# PLD_RadFET_Watchdog.net
KiCad netlist of a schematic drawn in Altium Designer
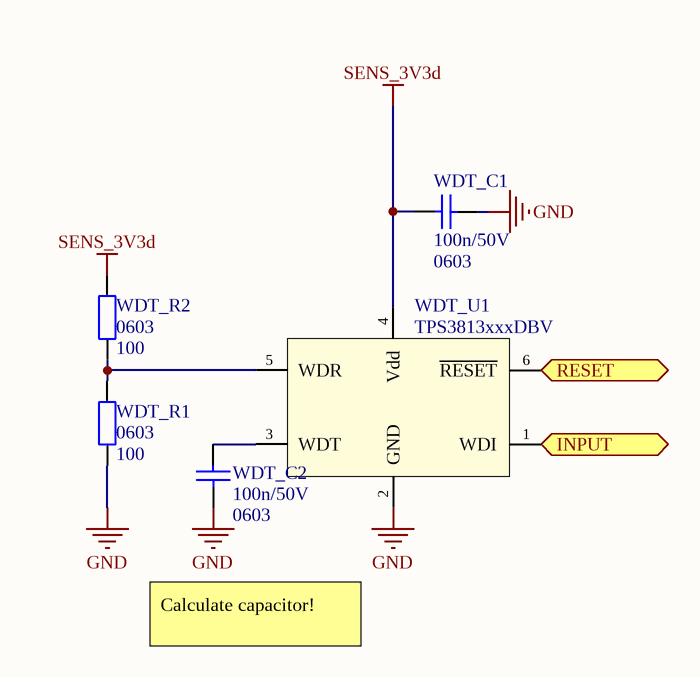
[diagram p0: PLD_RadFET_Watchdog.SchDoc]

(export (version "E")
  (design (tool "Eeschema 10.0.6"))
  (components
    (comp (ref "WDT_C1")
      (value "100n/50V")
      (footprint "SMD_Capacitor_0603")
      (description "Ceramic Cap Kemet COTS 100n/50V X7R 0603")
      (fields
        (field (name "MANUFACTURER") "Kemet")
        (field (name "MANUFACTURERPARTNUMBER") "C0603T104K5RALTU")
        (field (name "PACKAGE") "0603")
      )
      (libsource (lib "capacitors") (part "Cer_C0603T104K5RALTU"))
    )
    (comp (ref "WDT_C2")
      (value "100n/50V")
      (footprint "SMD_Capacitor_0603")
      (description "Ceramic Cap Kemet COTS 100n/50V X7R 0603")
      (fields
        (field (name "MANUFACTURER") "Kemet")
        (field (name "MANUFACTURERPARTNUMBER") "C0603T104K5RALTU")
        (field (name "PACKAGE") "0603")
      )
      (libsource (lib "capacitors") (part "Cer_C0603T104K5RALTU"))
    )
    (comp (ref "WDT_R1")
      (value "0603")
      (footprint "SMD_Resistor_0603")
      (description "Resistor")
      (fields (field (name "ALTIUM_VALUE") "100") (field (name "PUBLISHER") "Altium Limited"))
      (libsource (lib "Miscellaneous Devices") (part "Res2"))
    )
    (comp (ref "WDT_R2")
      (value "0603")
      (footprint "SMD_Resistor_0603")
      (description "Resistor")
      (fields (field (name "ALTIUM_VALUE") "100") (field (name "PUBLISHER") "Altium Limited"))
      (libsource (lib "Miscellaneous Devices") (part "Res2"))
    )
    (comp (ref "WDT_U1")
      (value "TPS3813xxxDBV")
      (footprint "SOT23-6")
      (description "Processor Supervisory Circuits with Window-Watchdog.")
      (fields (field (name "MANUFACTURER") "Texas Instruments"))
      (libsource (lib "microcircuits_other-functions") (part "TPS3813xxxDBV"))
    )
  )
  (nets
    (net (code "1") (name "/INPUT") (class "Default")
      (node (ref "WDT_U1") (pin "1") (pinfunction "WDI_1") (pintype "passive"))
    )
    (net (code "2") (name "/RESET") (class "Default")
      (node (ref "WDT_U1") (pin "6") (pinfunction "~{RESET}_6") (pintype "passive"))
    )
    (net (code "3") (name "GND") (class "Default")
      (node (ref "WDT_C1") (pin "2") (pinfunction "2_2") (pintype "passive"))
      (node (ref "WDT_C2") (pin "2") (pinfunction "2_2") (pintype "passive"))
      (node (ref "WDT_R1") (pin "1") (pinfunction "1_1") (pintype "passive"))
      (node (ref "WDT_U1") (pin "2") (pinfunction "GND_2") (pintype "passive"))
    )
    (net (code "4") (name "Net-(WDT_U1-WDR)") (class "Default")
      (node (ref "WDT_R1") (pin "2") (pinfunction "2_2") (pintype "passive"))
      (node (ref "WDT_R2") (pin "1") (pinfunction "1_1") (pintype "passive"))
      (node (ref "WDT_U1") (pin "5") (pinfunction "WDR_5") (pintype "passive"))
    )
    (net (code "5") (name "Net-(WDT_U1-WDT)") (class "Default")
      (node (ref "WDT_C2") (pin "1") (pinfunction "1_1") (pintype "passive"))
      (node (ref "WDT_U1") (pin "3") (pinfunction "WDT_3") (pintype "passive"))
    )
    (net (code "6") (name "SENS_3V3d") (class "Default")
      (node (ref "WDT_C1") (pin "1") (pinfunction "1_1") (pintype "passive"))
      (node (ref "WDT_R2") (pin "2") (pinfunction "2_2") (pintype "passive"))
      (node (ref "WDT_U1") (pin "4") (pinfunction "Vdd_4") (pintype "passive"))
    )
  )
)
